# h-bridge2-draft2.net
KiCad netlist of a schematic drawn in EAGLE
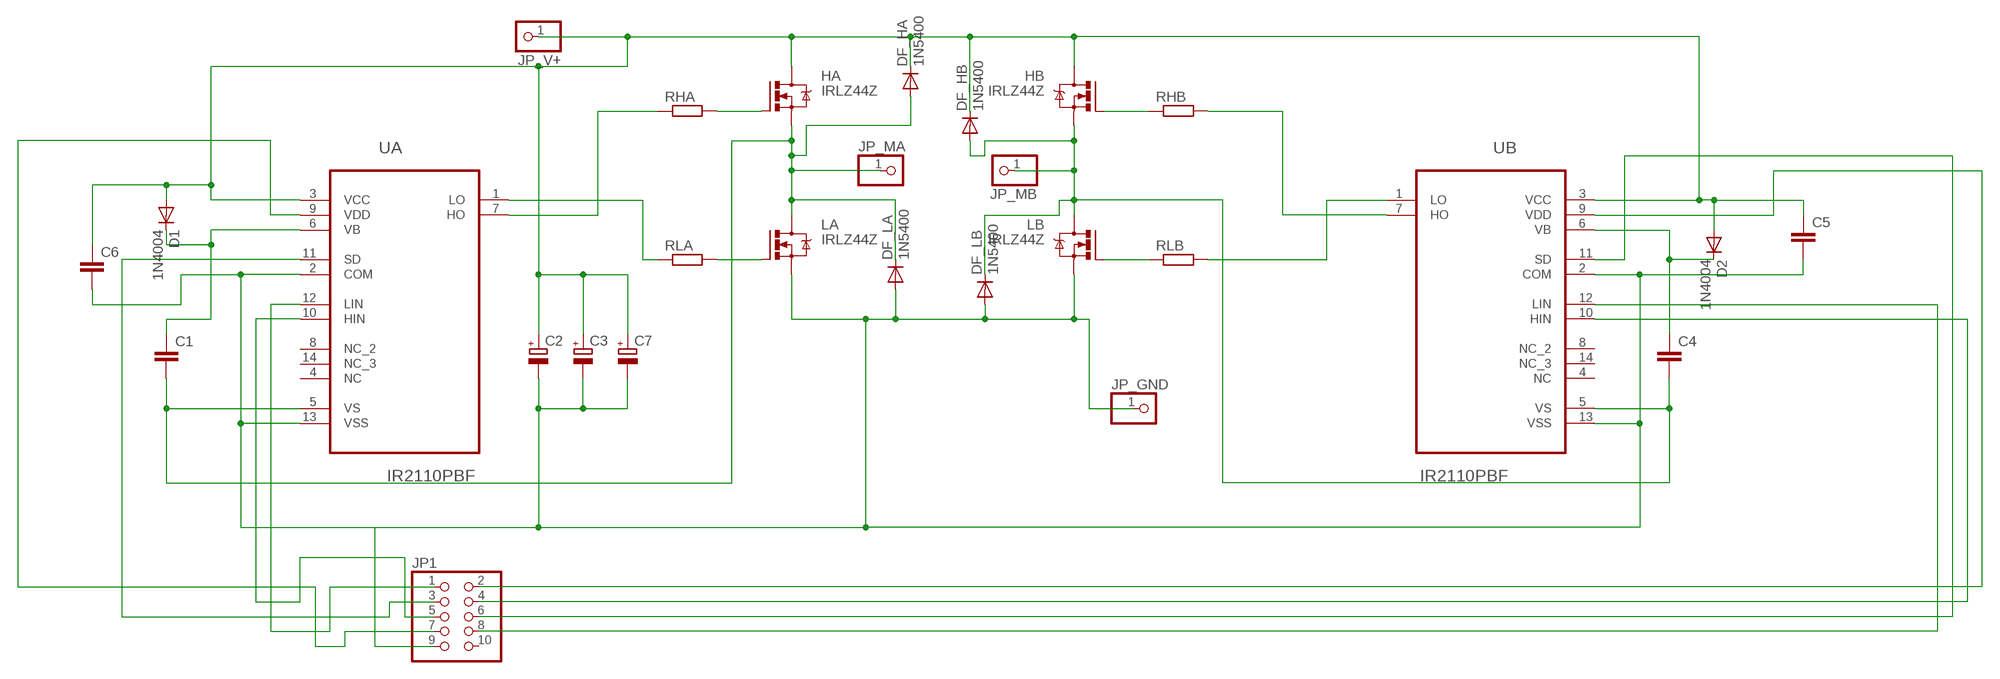
[diagram p0: schematic, sheet 1]

(export (version "E")
  (design (tool "Eeschema 10.0.6"))
  (components
    (comp (ref "C1")
      (value "C-EU025-025X050")
      (footprint "eagle-import:C025-025X050")
      (libsource (lib "eagle-import") (part "C-EU025-025X050"))
    )
    (comp (ref "C2")
      (value "CPOL-EUE5-13")
      (footprint "eagle-import:E5-13")
      (libsource (lib "eagle-import") (part "CPOL-EUE5-13"))
    )
    (comp (ref "C3")
      (value "CPOL-EUE5-13")
      (footprint "eagle-import:E5-13")
      (libsource (lib "eagle-import") (part "CPOL-EUE5-13"))
    )
    (comp (ref "C4")
      (value "C-EU025-025X050")
      (footprint "eagle-import:C025-025X050")
      (libsource (lib "eagle-import") (part "C-EU025-025X050"))
    )
    (comp (ref "C5")
      (value "C-EU025-025X050")
      (footprint "eagle-import:C025-025X050")
      (libsource (lib "eagle-import") (part "C-EU025-025X050"))
    )
    (comp (ref "C6")
      (value "C-EU025-025X050")
      (footprint "eagle-import:C025-025X050")
      (libsource (lib "eagle-import") (part "C-EU025-025X050"))
    )
    (comp (ref "C7")
      (value "CPOL-EUE5-13")
      (footprint "eagle-import:E5-13")
      (libsource (lib "eagle-import") (part "CPOL-EUE5-13"))
    )
    (comp (ref "D1")
      (value "1N4004")
      (footprint "eagle-import:DO41-10")
      (libsource (lib "eagle-import") (part "1N4004"))
    )
    (comp (ref "D2")
      (value "1N4004")
      (footprint "eagle-import:DO41-10")
      (libsource (lib "eagle-import") (part "1N4004"))
    )
    (comp (ref "DF_HA")
      (value "1N5400")
      (footprint "eagle-import:DO201-15")
      (libsource (lib "eagle-import") (part "1N5400"))
    )
    (comp (ref "DF_HB")
      (value "1N5400")
      (footprint "eagle-import:DO201-15")
      (libsource (lib "eagle-import") (part "1N5400"))
    )
    (comp (ref "DF_LA")
      (value "1N5400")
      (footprint "eagle-import:DO201-15")
      (libsource (lib "eagle-import") (part "1N5400"))
    )
    (comp (ref "DF_LB")
      (value "1N5400")
      (footprint "eagle-import:DO201-15")
      (libsource (lib "eagle-import") (part "1N5400"))
    )
    (comp (ref "HA")
      (value "IRLZ44Z")
      (footprint "eagle-import:TO220BH")
      (libsource (lib "eagle-import") (part "IRLZ44Z"))
    )
    (comp (ref "HB")
      (value "IRLZ44Z")
      (footprint "eagle-import:TO220BH")
      (libsource (lib "eagle-import") (part "IRLZ44Z"))
    )
    (comp (ref "JP1")
      (value "PINHD-2X5")
      (footprint "eagle-import:2X05")
      (libsource (lib "eagle-import") (part "PINHD-2X5"))
    )
    (comp (ref "JP_GND")
      (value "PINHD-1X1")
      (footprint "eagle-import:1X01")
      (libsource (lib "eagle-import") (part "PINHD-1X1"))
    )
    (comp (ref "JP_MA")
      (value "PINHD-1X1")
      (footprint "eagle-import:1X01")
      (libsource (lib "eagle-import") (part "PINHD-1X1"))
    )
    (comp (ref "JP_MB")
      (value "PINHD-1X1")
      (footprint "eagle-import:1X01")
      (libsource (lib "eagle-import") (part "PINHD-1X1"))
    )
    (comp (ref "JP_V+")
      (value "PINHD-1X1")
      (footprint "eagle-import:1X01")
      (libsource (lib "eagle-import") (part "PINHD-1X1"))
    )
    (comp (ref "LA")
      (value "IRLZ44Z")
      (footprint "eagle-import:TO220BH")
      (libsource (lib "eagle-import") (part "IRLZ44Z"))
    )
    (comp (ref "LB")
      (value "IRLZ44Z")
      (footprint "eagle-import:TO220BH")
      (libsource (lib "eagle-import") (part "IRLZ44Z"))
    )
    (comp (ref "RHA")
      (value "R-EU_0411/15")
      (footprint "eagle-import:0411_15")
      (libsource (lib "eagle-import") (part "R-EU_0411/15"))
    )
    (comp (ref "RHB")
      (value "R-EU_0411/15")
      (footprint "eagle-import:0411_15")
      (libsource (lib "eagle-import") (part "R-EU_0411/15"))
    )
    (comp (ref "RLA")
      (value "R-EU_0411/15")
      (footprint "eagle-import:0411_15")
      (libsource (lib "eagle-import") (part "R-EU_0411/15"))
    )
    (comp (ref "RLB")
      (value "R-EU_0411/15")
      (footprint "eagle-import:0411_15")
      (libsource (lib "eagle-import") (part "R-EU_0411/15"))
    )
    (comp (ref "UA")
      (value "IR2110PBF")
      (footprint "eagle-import:DIP254P762X533-14")
      (libsource (lib "eagle-import") (part "IR2110PBF"))
    )
    (comp (ref "UB")
      (value "IR2110PBF")
      (footprint "eagle-import:DIP254P762X533-14")
      (libsource (lib "eagle-import") (part "IR2110PBF"))
    )
  )
  (nets
    (net (code "1") (name "Net-(HA-PadG)") (class "Default")
      (node (ref "HA") (pin "G") (pinfunction "G_G") (pintype "passive"))
      (node (ref "RHA") (pin "2") (pinfunction "2_2") (pintype "passive"))
    )
    (net (code "2") (name "Net-(HB-PadG)") (class "Default")
      (node (ref "HB") (pin "G") (pinfunction "G_G") (pintype "passive"))
      (node (ref "RHB") (pin "1") (pinfunction "1_1") (pintype "passive"))
    )
    (net (code "3") (name "Net-(LA-PadG)") (class "Default")
      (node (ref "LA") (pin "G") (pinfunction "G_G") (pintype "passive"))
      (node (ref "RLA") (pin "2") (pinfunction "2_2") (pintype "passive"))
    )
    (net (code "4") (name "Net-(LB-PadG)") (class "Default")
      (node (ref "LB") (pin "G") (pinfunction "G_G") (pintype "passive"))
      (node (ref "RLB") (pin "1") (pinfunction "1_1") (pintype "passive"))
    )
    (net (code "5") (name "Net-(UA-COM)") (class "Default")
      (node (ref "C2") (pin "-") (pinfunction "-_-") (pintype "passive"))
      (node (ref "C3") (pin "-") (pinfunction "-_-") (pintype "passive"))
      (node (ref "C5") (pin "2") (pinfunction "2_2") (pintype "passive"))
      (node (ref "C6") (pin "2") (pinfunction "2_2") (pintype "passive"))
      (node (ref "C7") (pin "-") (pinfunction "-_-") (pintype "passive"))
      (node (ref "DF_LA") (pin "A") (pinfunction "A_A") (pintype "passive"))
      (node (ref "DF_LB") (pin "A") (pinfunction "A_A") (pintype "passive"))
      (node (ref "JP1") (pin "9") (pinfunction "9_9") (pintype "passive"))
      (node (ref "JP_GND") (pin "1") (pinfunction "1_1") (pintype "passive"))
      (node (ref "LA") (pin "S") (pinfunction "S_S") (pintype "passive"))
      (node (ref "LB") (pin "S") (pinfunction "S_S") (pintype "passive"))
      (node (ref "UA") (pin "13") (pinfunction "VSS_13") (pintype "power_in"))
      (node (ref "UA") (pin "2") (pinfunction "COM_2") (pintype "passive"))
      (node (ref "UB") (pin "13") (pinfunction "VSS_13") (pintype "power_in"))
      (node (ref "UB") (pin "2") (pinfunction "COM_2") (pintype "passive"))
    )
    (net (code "6") (name "Net-(UA-HIN)") (class "Default")
      (node (ref "JP1") (pin "5") (pinfunction "5_5") (pintype "passive"))
      (node (ref "UA") (pin "10") (pinfunction "HIN_10") (pintype "input"))
    )
    (net (code "7") (name "Net-(UA-HO)") (class "Default")
      (node (ref "RHA") (pin "1") (pinfunction "1_1") (pintype "passive"))
      (node (ref "UA") (pin "7") (pinfunction "HO_7") (pintype "output"))
    )
    (net (code "8") (name "Net-(UA-LIN)") (class "Default")
      (node (ref "JP1") (pin "1") (pinfunction "1_1") (pintype "passive"))
      (node (ref "UA") (pin "12") (pinfunction "LIN_12") (pintype "input"))
    )
    (net (code "9") (name "Net-(UA-LO)") (class "Default")
      (node (ref "RLA") (pin "1") (pinfunction "1_1") (pintype "passive"))
      (node (ref "UA") (pin "1") (pinfunction "LO_1") (pintype "output"))
    )
    (net (code "10") (name "Net-(UA-SD)") (class "Default")
      (node (ref "JP1") (pin "3") (pinfunction "3_3") (pintype "passive"))
      (node (ref "UA") (pin "11") (pinfunction "SD_11") (pintype "input"))
    )
    (net (code "11") (name "Net-(UA-VB)") (class "Default")
      (node (ref "C1") (pin "1") (pinfunction "1_1") (pintype "passive"))
      (node (ref "D1") (pin "C") (pinfunction "C_C") (pintype "passive"))
      (node (ref "UA") (pin "6") (pinfunction "VB_6") (pintype "power_in"))
    )
    (net (code "12") (name "Net-(UA-VCC)") (class "Default")
      (node (ref "C2") (pin "+") (pinfunction "+_+") (pintype "passive"))
      (node (ref "C3") (pin "+") (pinfunction "+_+") (pintype "passive"))
      (node (ref "C5") (pin "1") (pinfunction "1_1") (pintype "passive"))
      (node (ref "C6") (pin "1") (pinfunction "1_1") (pintype "passive"))
      (node (ref "C7") (pin "+") (pinfunction "+_+") (pintype "passive"))
      (node (ref "D1") (pin "A") (pinfunction "A_A") (pintype "passive"))
      (node (ref "D2") (pin "A") (pinfunction "A_A") (pintype "passive"))
      (node (ref "DF_HA") (pin "C") (pinfunction "C_C") (pintype "passive"))
      (node (ref "DF_HB") (pin "C") (pinfunction "C_C") (pintype "passive"))
      (node (ref "HA") (pin "D") (pinfunction "D_D") (pintype "passive"))
      (node (ref "HB") (pin "D") (pinfunction "D_D") (pintype "passive"))
      (node (ref "JP_V+") (pin "1") (pinfunction "1_1") (pintype "passive"))
      (node (ref "UA") (pin "3") (pinfunction "VCC_3") (pintype "power_in"))
      (node (ref "UB") (pin "3") (pinfunction "VCC_3") (pintype "power_in"))
    )
    (net (code "13") (name "Net-(UA-VDD)") (class "Default")
      (node (ref "JP1") (pin "7") (pinfunction "7_7") (pintype "passive"))
      (node (ref "UA") (pin "9") (pinfunction "VDD_9") (pintype "power_in"))
    )
    (net (code "14") (name "Net-(UA-VS)") (class "Default")
      (node (ref "C1") (pin "2") (pinfunction "2_2") (pintype "passive"))
      (node (ref "DF_HA") (pin "A") (pinfunction "A_A") (pintype "passive"))
      (node (ref "DF_LA") (pin "C") (pinfunction "C_C") (pintype "passive"))
      (node (ref "HA") (pin "S") (pinfunction "S_S") (pintype "passive"))
      (node (ref "JP_MA") (pin "1") (pinfunction "1_1") (pintype "passive"))
      (node (ref "LA") (pin "D") (pinfunction "D_D") (pintype "passive"))
      (node (ref "UA") (pin "5") (pinfunction "VS_5") (pintype "power_in"))
    )
    (net (code "15") (name "Net-(UB-HIN)") (class "Default")
      (node (ref "JP1") (pin "4") (pinfunction "4_4") (pintype "passive"))
      (node (ref "UB") (pin "10") (pinfunction "HIN_10") (pintype "input"))
    )
    (net (code "16") (name "Net-(UB-HO)") (class "Default")
      (node (ref "RHB") (pin "2") (pinfunction "2_2") (pintype "passive"))
      (node (ref "UB") (pin "7") (pinfunction "HO_7") (pintype "output"))
    )
    (net (code "17") (name "Net-(UB-LIN)") (class "Default")
      (node (ref "JP1") (pin "8") (pinfunction "8_8") (pintype "passive"))
      (node (ref "UB") (pin "12") (pinfunction "LIN_12") (pintype "input"))
    )
    (net (code "18") (name "Net-(UB-LO)") (class "Default")
      (node (ref "RLB") (pin "2") (pinfunction "2_2") (pintype "passive"))
      (node (ref "UB") (pin "1") (pinfunction "LO_1") (pintype "output"))
    )
    (net (code "19") (name "Net-(UB-SD)") (class "Default")
      (node (ref "JP1") (pin "6") (pinfunction "6_6") (pintype "passive"))
      (node (ref "UB") (pin "11") (pinfunction "SD_11") (pintype "input"))
    )
    (net (code "20") (name "Net-(UB-VB)") (class "Default")
      (node (ref "C4") (pin "1") (pinfunction "1_1") (pintype "passive"))
      (node (ref "D2") (pin "C") (pinfunction "C_C") (pintype "passive"))
      (node (ref "UB") (pin "6") (pinfunction "VB_6") (pintype "power_in"))
    )
    (net (code "21") (name "Net-(UB-VDD)") (class "Default")
      (node (ref "JP1") (pin "2") (pinfunction "2_2") (pintype "passive"))
      (node (ref "UB") (pin "9") (pinfunction "VDD_9") (pintype "power_in"))
    )
    (net (code "22") (name "Net-(UB-VS)") (class "Default")
      (node (ref "C4") (pin "2") (pinfunction "2_2") (pintype "passive"))
      (node (ref "DF_HB") (pin "A") (pinfunction "A_A") (pintype "passive"))
      (node (ref "DF_LB") (pin "C") (pinfunction "C_C") (pintype "passive"))
      (node (ref "HB") (pin "S") (pinfunction "S_S") (pintype "passive"))
      (node (ref "JP_MB") (pin "1") (pinfunction "1_1") (pintype "passive"))
      (node (ref "LB") (pin "D") (pinfunction "D_D") (pintype "passive"))
      (node (ref "UB") (pin "5") (pinfunction "VS_5") (pintype "power_in"))
    )
    (net (code "23") (name "unconnected-(JP1-Pad10)") (class "Default")
      (node (ref "JP1") (pin "10") (pinfunction "10_10") (pintype "passive"))
    )
    (net (code "24") (name "unconnected-(UA-NC-Pad4)") (class "Default")
      (node (ref "UA") (pin "4") (pinfunction "NC_4") (pintype "no_connect"))
    )
    (net (code "25") (name "unconnected-(UA-NC_2-Pad8)") (class "Default")
      (node (ref "UA") (pin "8") (pinfunction "NC_2_8") (pintype "no_connect"))
    )
    (net (code "26") (name "unconnected-(UA-NC_3-Pad14)") (class "Default")
      (node (ref "UA") (pin "14") (pinfunction "NC_3_14") (pintype "no_connect"))
    )
    (net (code "27") (name "unconnected-(UB-NC-Pad4)") (class "Default")
      (node (ref "UB") (pin "4") (pinfunction "NC_4") (pintype "no_connect"))
    )
    (net (code "28") (name "unconnected-(UB-NC_2-Pad8)") (class "Default")
      (node (ref "UB") (pin "8") (pinfunction "NC_2_8") (pintype "no_connect"))
    )
    (net (code "29") (name "unconnected-(UB-NC_3-Pad14)") (class "Default")
      (node (ref "UB") (pin "14") (pinfunction "NC_3_14") (pintype "no_connect"))
    )
  )
)
